# Seven-Seg_Displays.net
KiCad netlist of a schematic drawn in Altium Designer
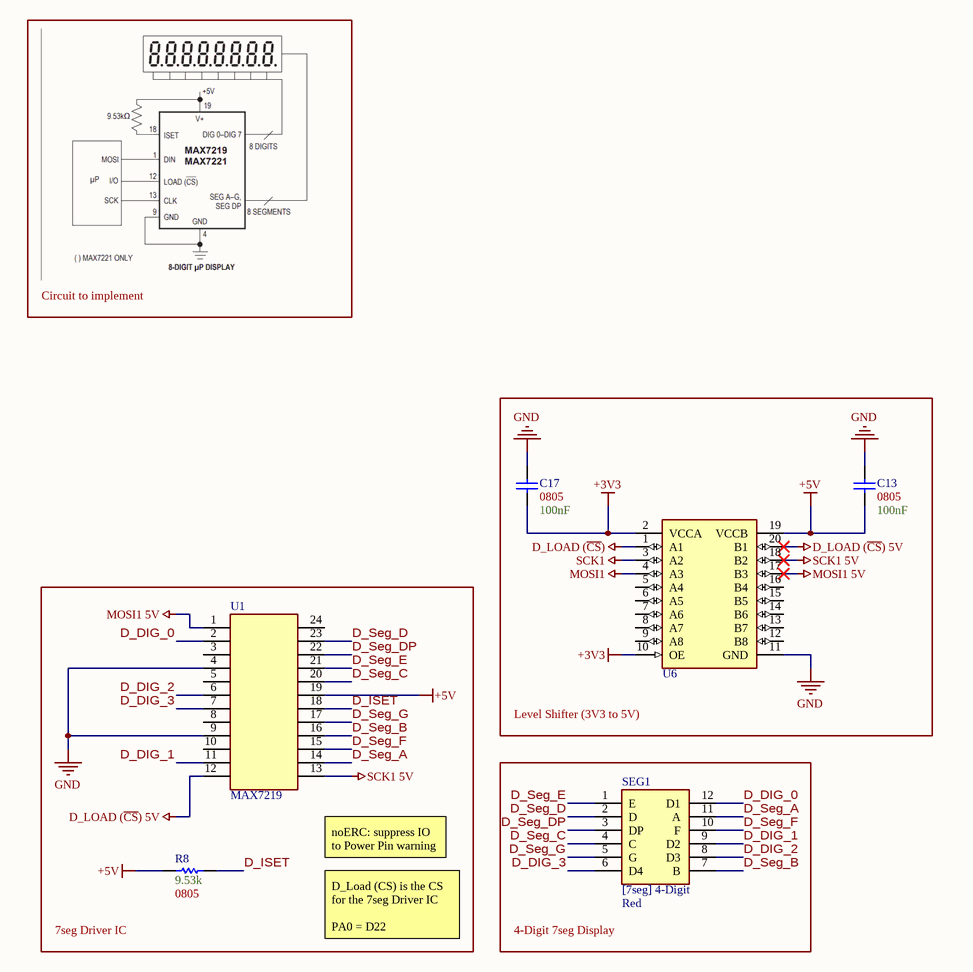
[diagram p0: Seven-Seg Displays.SchDoc]

(export (version "E")
  (design (tool "Eeschema 10.0.6"))
  (components
    (comp (ref "C13")
      (value "[Cap] SMD Nonpolarized")
      (footprint "[Cap] SMD 0805")
      (fields (field (name "SIZE PACKAGE") "0805") (field (name "CAPACITANCE") "100nF"))
      (libsource (lib "RADM Components") (part "[Cap] SMD Nonpolarized"))
    )
    (comp (ref "C17")
      (value "[Cap] SMD Nonpolarized")
      (footprint "[Cap] SMD 0805")
      (fields (field (name "SIZE PACKAGE") "0805") (field (name "CAPACITANCE") "100nF"))
      (libsource (lib "RADM Components") (part "[Cap] SMD Nonpolarized"))
    )
    (comp (ref "R8")
      (value "[Res] SMD Resistor")
      (footprint "[Res] SMD 0805")
      (fields (field (name "RESISTANCE") "9.53k") (field (name "SIZE PACKAGE") "0805"))
      (libsource (lib "RADM Components") (part "[Res] SMD Resistor"))
    )
    (comp (ref "SEG1")
      (value "[7seg] 4-Digit")
      (footprint "[7seg] 4-Digit")
      (fields (field (name "MOUSER PART #") "474-COM-11405") (field (name "COLOR") "Red"))
      (libsource (lib "RADM Components") (part "[7seg] 4-Digit"))
    )
    (comp (ref "U1")
      (value "MAX7219")
      (footprint "[DIP IC] 24pin, Socket")
      (libsource (lib "RADM Components") (part "[DIP IC] 24pin"))
    )
    (comp (ref "U6")
      (value "[IC] Level Shifter (2)")
      (footprint "[IC] Level Shifter (2)")
      (description "TXS0108EQPWRQ1")
      (libsource (lib "RADM Components") (part "[IC] Level Shifter (2)"))
    )
  )
  (nets
    (net (code "1") (name "+3V3") (class "Default")
      (node (ref "C17") (pin "1") (pinfunction "1_1") (pintype "passive"))
      (node (ref "U6") (pin "10") (pinfunction "OE_10") (pintype "input"))
      (node (ref "U6") (pin "2") (pinfunction "VCCA_2") (pintype "power_in"))
    )
    (net (code "2") (name "+5V") (class "Default")
      (node (ref "C13") (pin "1") (pinfunction "1_1") (pintype "passive"))
      (node (ref "R8") (pin "1") (pinfunction "1_1") (pintype "passive"))
      (node (ref "U1") (pin "19") (pintype "power_in"))
      (node (ref "U6") (pin "19") (pinfunction "VCCB_19") (pintype "power_in"))
    )
    (net (code "3") (name "/D_DIG_0") (class "Default")
      (node (ref "SEG1") (pin "12") (pinfunction "D1_12") (pintype "power_in"))
      (node (ref "U1") (pin "2") (pintype "power_in"))
    )
    (net (code "4") (name "/D_DIG_1") (class "Default")
      (node (ref "SEG1") (pin "9") (pinfunction "D2_9") (pintype "power_in"))
      (node (ref "U1") (pin "11") (pintype "power_in"))
    )
    (net (code "5") (name "/D_DIG_2") (class "Default")
      (node (ref "SEG1") (pin "8") (pinfunction "D3_8") (pintype "power_in"))
      (node (ref "U1") (pin "6") (pintype "power_in"))
    )
    (net (code "6") (name "/D_DIG_3") (class "Default")
      (node (ref "SEG1") (pin "6") (pinfunction "D4_6") (pintype "power_in"))
      (node (ref "U1") (pin "7") (pintype "power_in"))
    )
    (net (code "7") (name "/D_ISET") (class "Default")
      (node (ref "R8") (pin "2") (pinfunction "2_2") (pintype "passive"))
      (node (ref "U1") (pin "18") (pintype "power_in"))
    )
    (net (code "8") (name "/D_Seg_A") (class "Default")
      (node (ref "SEG1") (pin "11") (pinfunction "A_11") (pintype "power_in"))
      (node (ref "U1") (pin "14") (pintype "power_in"))
    )
    (net (code "9") (name "/D_Seg_B") (class "Default")
      (node (ref "SEG1") (pin "7") (pinfunction "B_7") (pintype "power_in"))
      (node (ref "U1") (pin "16") (pintype "power_in"))
    )
    (net (code "10") (name "/D_Seg_C") (class "Default")
      (node (ref "SEG1") (pin "4") (pinfunction "C_4") (pintype "power_in"))
      (node (ref "U1") (pin "20") (pintype "power_in"))
    )
    (net (code "11") (name "/D_Seg_D") (class "Default")
      (node (ref "SEG1") (pin "2") (pinfunction "D_2") (pintype "power_in"))
      (node (ref "U1") (pin "23") (pintype "power_in"))
    )
    (net (code "12") (name "/D_Seg_DP") (class "Default")
      (node (ref "SEG1") (pin "3") (pinfunction "DP_3") (pintype "power_in"))
      (node (ref "U1") (pin "22") (pintype "power_in"))
    )
    (net (code "13") (name "/D_Seg_E") (class "Default")
      (node (ref "SEG1") (pin "1") (pinfunction "E_1") (pintype "power_in"))
      (node (ref "U1") (pin "21") (pintype "power_in"))
    )
    (net (code "14") (name "/D_Seg_F") (class "Default")
      (node (ref "SEG1") (pin "10") (pinfunction "F_10") (pintype "power_in"))
      (node (ref "U1") (pin "15") (pintype "power_in"))
    )
    (net (code "15") (name "/D_Seg_G") (class "Default")
      (node (ref "SEG1") (pin "5") (pinfunction "G_5") (pintype "power_in"))
      (node (ref "U1") (pin "17") (pintype "power_in"))
    )
    (net (code "16") (name "D_LOAD (~{CS})") (class "Default")
      (node (ref "U6") (pin "1") (pinfunction "A1_1") (pintype "bidirectional"))
    )
    (net (code "17") (name "D_LOAD (~{CS}) 5V") (class "Default")
      (node (ref "U1") (pin "12") (pintype "power_in"))
      (node (ref "U6") (pin "20") (pinfunction "B1_20") (pintype "bidirectional"))
    )
    (net (code "18") (name "GND") (class "Default")
      (node (ref "C13") (pin "2") (pinfunction "2_2") (pintype "passive"))
      (node (ref "C17") (pin "2") (pinfunction "2_2") (pintype "passive"))
      (node (ref "U1") (pin "4") (pintype "power_in"))
      (node (ref "U1") (pin "9") (pintype "power_in"))
      (node (ref "U6") (pin "11") (pinfunction "GND_11") (pintype "power_in"))
    )
    (net (code "19") (name "MOSI1") (class "Default")
      (node (ref "U6") (pin "4") (pinfunction "A3_4") (pintype "bidirectional"))
    )
    (net (code "20") (name "MOSI1 5V") (class "Default")
      (node (ref "U1") (pin "1") (pintype "power_in"))
      (node (ref "U6") (pin "17") (pinfunction "B3_17") (pintype "bidirectional"))
    )
    (net (code "21") (name "SCK1") (class "Default")
      (node (ref "U6") (pin "3") (pinfunction "A2_3") (pintype "bidirectional"))
    )
    (net (code "22") (name "SCK1 5V") (class "Default")
      (node (ref "U1") (pin "13") (pintype "power_in"))
      (node (ref "U6") (pin "18") (pinfunction "B2_18") (pintype "bidirectional"))
    )
    (net (code "23") (name "unconnected-(U1-Pad3)") (class "Default")
      (node (ref "U1") (pin "3") (pintype "power_in"))
    )
    (net (code "24") (name "unconnected-(U1-Pad5)") (class "Default")
      (node (ref "U1") (pin "5") (pintype "power_in"))
    )
    (net (code "25") (name "unconnected-(U1-Pad8)") (class "Default")
      (node (ref "U1") (pin "8") (pintype "power_in"))
    )
    (net (code "26") (name "unconnected-(U1-Pad10)") (class "Default")
      (node (ref "U1") (pin "10") (pintype "power_in"))
    )
    (net (code "27") (name "unconnected-(U1-Pad24)") (class "Default")
      (node (ref "U1") (pin "24") (pintype "power_in"))
    )
    (net (code "28") (name "unconnected-(U6-A4-Pad5)") (class "Default")
      (node (ref "U6") (pin "5") (pinfunction "A4_5") (pintype "bidirectional"))
    )
    (net (code "29") (name "unconnected-(U6-A5-Pad6)") (class "Default")
      (node (ref "U6") (pin "6") (pinfunction "A5_6") (pintype "bidirectional"))
    )
    (net (code "30") (name "unconnected-(U6-A6-Pad7)") (class "Default")
      (node (ref "U6") (pin "7") (pinfunction "A6_7") (pintype "bidirectional"))
    )
    (net (code "31") (name "unconnected-(U6-A7-Pad8)") (class "Default")
      (node (ref "U6") (pin "8") (pinfunction "A7_8") (pintype "bidirectional"))
    )
    (net (code "32") (name "unconnected-(U6-A8-Pad9)") (class "Default")
      (node (ref "U6") (pin "9") (pinfunction "A8_9") (pintype "bidirectional"))
    )
    (net (code "33") (name "unconnected-(U6-B4-Pad16)") (class "Default")
      (node (ref "U6") (pin "16") (pinfunction "B4_16") (pintype "bidirectional"))
    )
    (net (code "34") (name "unconnected-(U6-B5-Pad15)") (class "Default")
      (node (ref "U6") (pin "15") (pinfunction "B5_15") (pintype "bidirectional"))
    )
    (net (code "35") (name "unconnected-(U6-B6-Pad14)") (class "Default")
      (node (ref "U6") (pin "14") (pinfunction "B6_14") (pintype "bidirectional"))
    )
    (net (code "36") (name "unconnected-(U6-B7-Pad13)") (class "Default")
      (node (ref "U6") (pin "13") (pinfunction "B7_13") (pintype "bidirectional"))
    )
    (net (code "37") (name "unconnected-(U6-B8-Pad12)") (class "Default")
      (node (ref "U6") (pin "12") (pinfunction "B8_12") (pintype "bidirectional"))
    )
  )
)
